# 3_1.net
KiCad netlist of a schematic drawn in Altium Designer
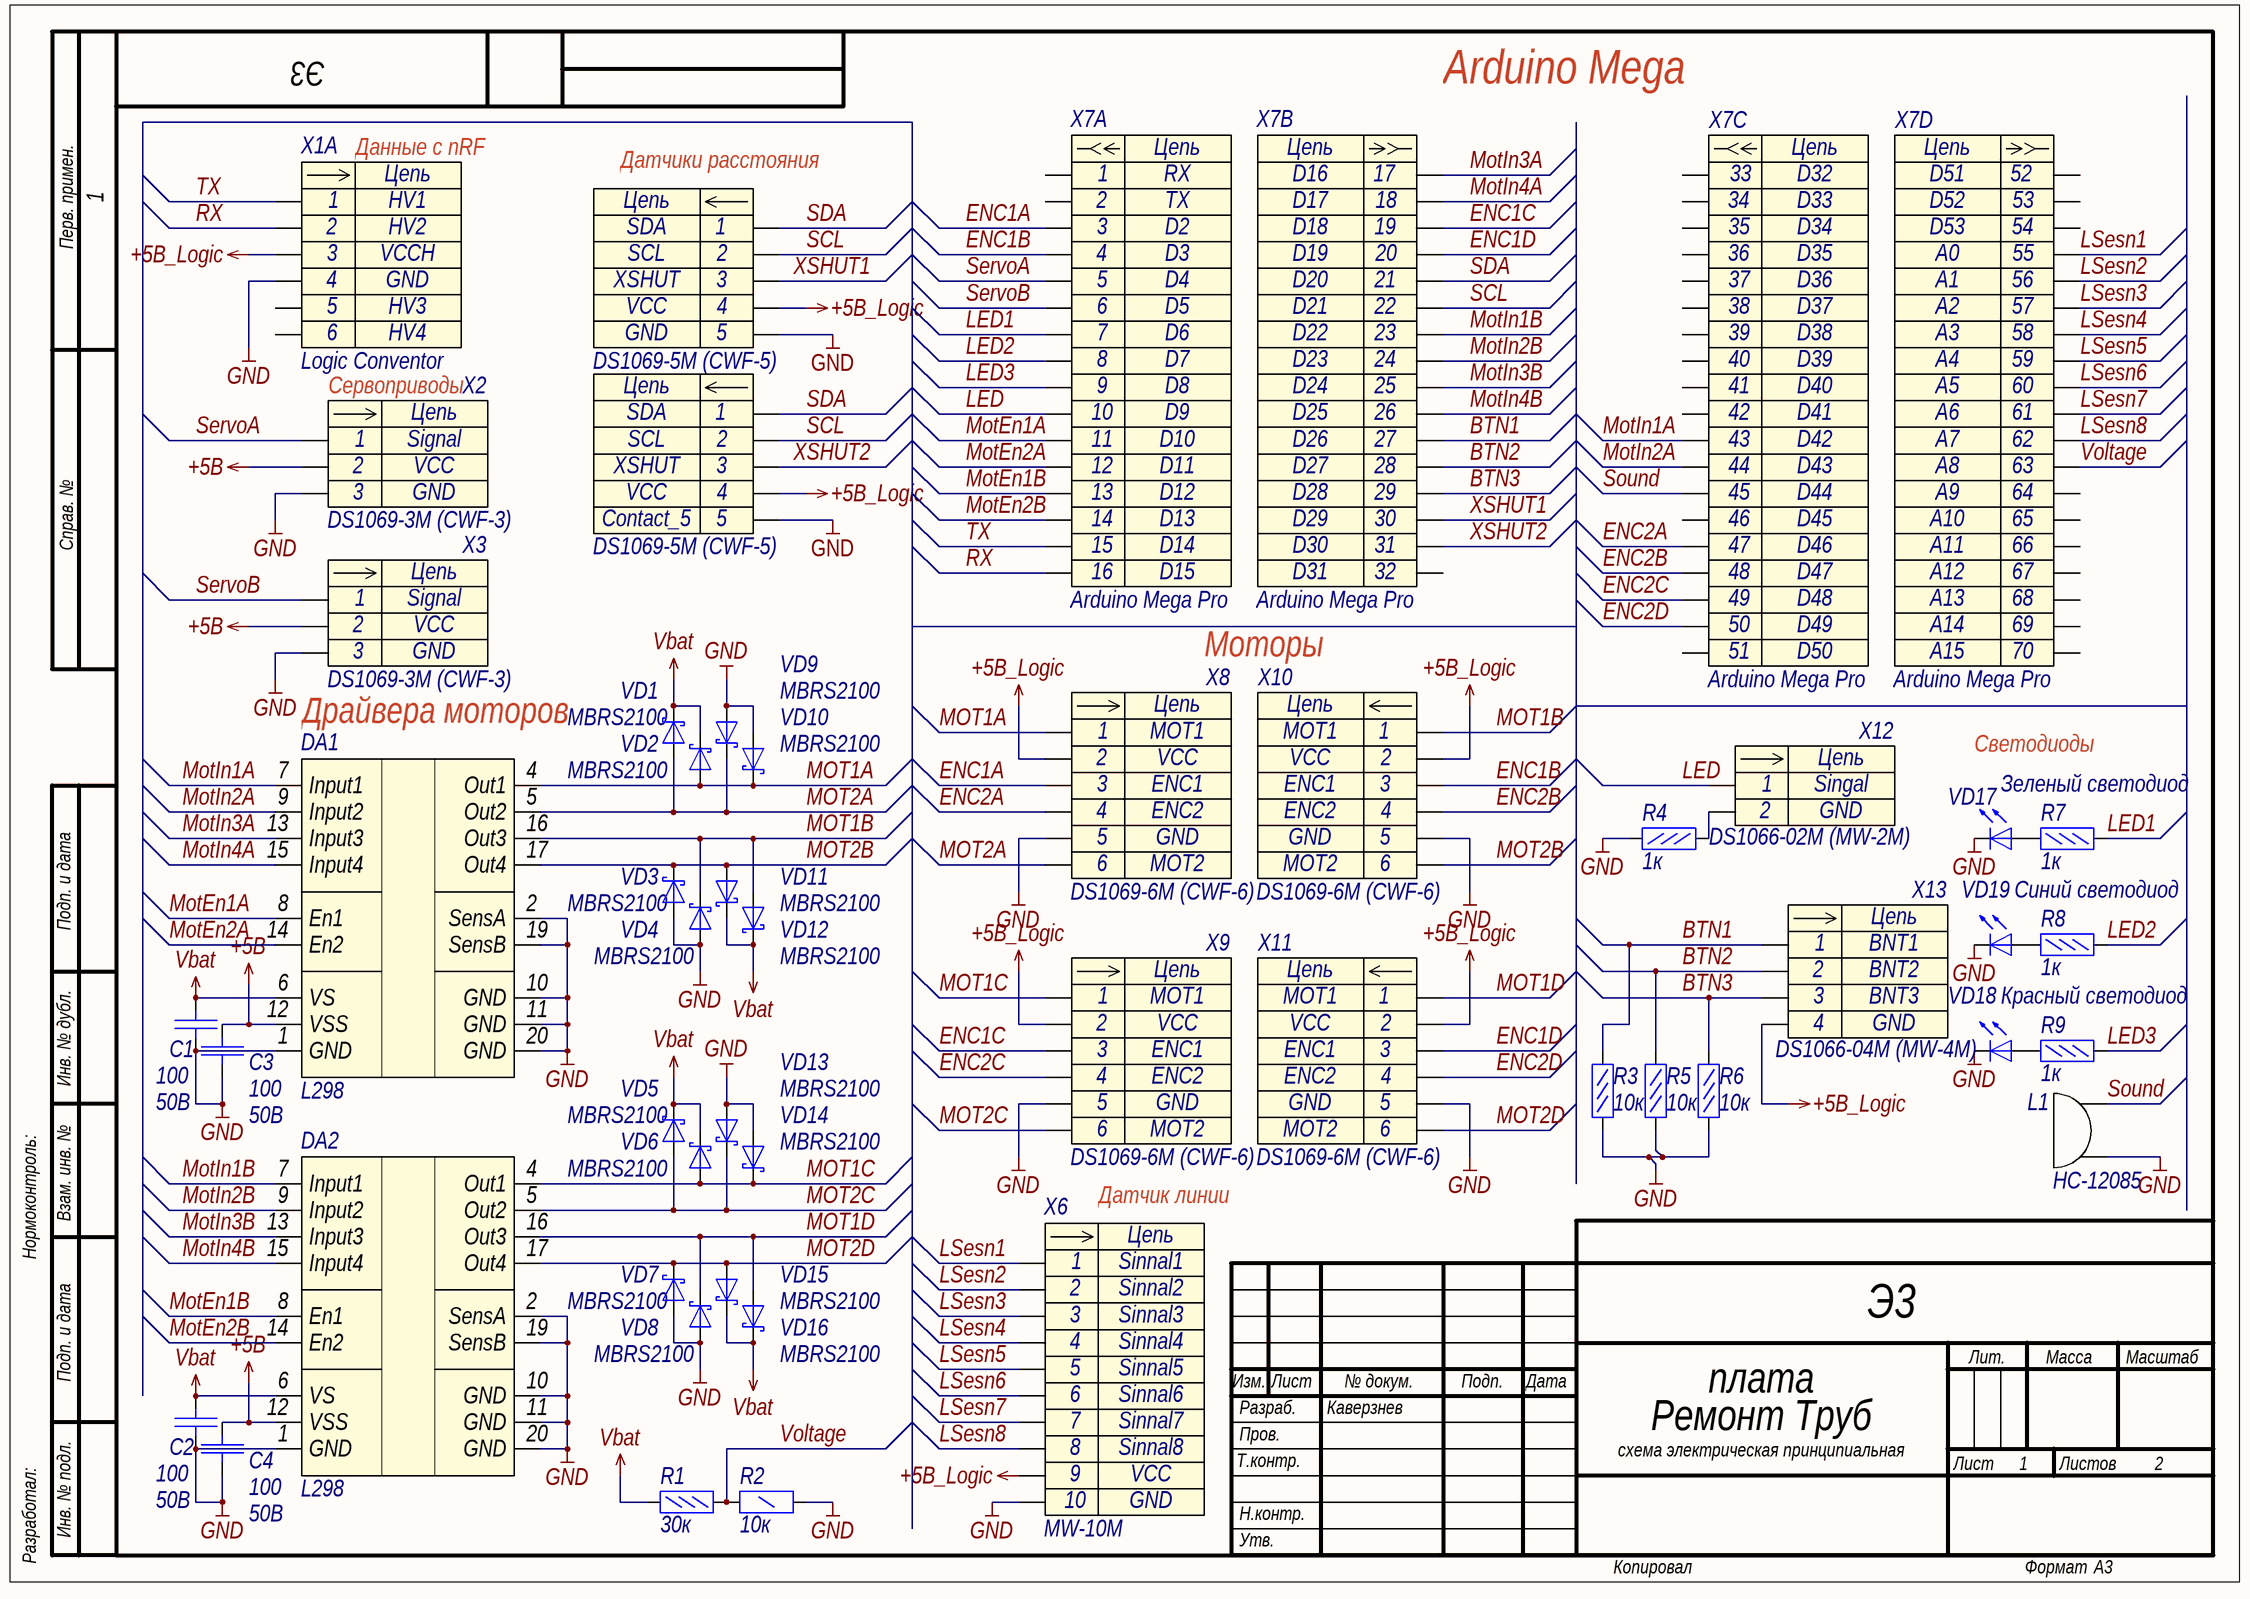
[diagram p0: Э3_1.SchDoc]

(export (version "E")
  (design (tool "Eeschema 10.0.6"))
  (components
    (comp (ref "C1")
      (value "100")
      (footprint "C0603")
      (description "Конденсатор кер. 100пФ 50В")
      (fields (field (name "MANUFACTURER") "Yageo") (field (name "VOLTAGE") "50В"))
      (libsource (lib "capacitors") (part "CC0603JRNPO9BN101"))
    )
    (comp (ref "C2")
      (value "100")
      (footprint "C0603")
      (description "Конденсатор кер. 100пФ 50В")
      (fields (field (name "MANUFACTURER") "Yageo") (field (name "VOLTAGE") "50В"))
      (libsource (lib "capacitors") (part "CC0603JRNPO9BN101"))
    )
    (comp (ref "C3")
      (value "100")
      (footprint "C0603")
      (description "Конденсатор кер. 100пФ 50В")
      (fields (field (name "MANUFACTURER") "Yageo") (field (name "VOLTAGE") "50В"))
      (libsource (lib "capacitors") (part "CC0603JRNPO9BN101"))
    )
    (comp (ref "C4")
      (value "100")
      (footprint "C0603")
      (description "Конденсатор кер. 100пФ 50В")
      (fields (field (name "MANUFACTURER") "Yageo") (field (name "VOLTAGE") "50В"))
      (libsource (lib "capacitors") (part "CC0603JRNPO9BN101"))
    )
    (comp (ref "DA1")
      (value "L298")
      (footprint "L298P")
      (description "Драйвер двигателя")
      (fields (field (name "MANUFACTURER") "China") (field (name "NAME") "L298"))
      (libsource (lib "ics") (part "L298"))
    )
    (comp (ref "DA2")
      (value "L298")
      (footprint "L298P")
      (description "Драйвер двигателя")
      (fields (field (name "MANUFACTURER") "China") (field (name "NAME") "L298"))
      (libsource (lib "ics") (part "L298"))
    )
    (comp (ref "L1")
      (value "HC-12085")
      (footprint "Buzzer")
      (fields (field (name "MANUFACTURER") "Epcos TDK") (field (name "NAME") "HC-12085"))
      (libsource (lib "ics") (part "HC-12085"))
    )
    (comp (ref "R1")
      (value "30к")
      (footprint "R0603")
      (description "Резистор 30кОм 0,063Вт 1%")
      (fields (field (name "MANUFACTURER") "YAGEO") (field (name "TOLERANCE") "1%"))
      (libsource (lib "resistors") (part "RC0603FR-0730KL"))
    )
    (comp (ref "R2")
      (value "10к")
      (footprint "R1206")
      (description "Резистор 10к 0,25Вт 1%")
      (fields (field (name "MANUFACTURER") "YAGEO"))
      (libsource (lib "resistors") (part "RC1206FR-0710KL"))
    )
    (comp (ref "R3")
      (value "10к")
      (footprint "R0603")
      (description "Резистор 10кОм 0,063Вт 1%")
      (fields (field (name "MANUFACTURER") "YAGEO") (field (name "TOLERANCE") "1%"))
      (libsource (lib "resistors") (part "RC0603FR-0710KL"))
    )
    (comp (ref "R4")
      (value "1к")
      (footprint "R0603")
      (description "Резистор 1кОм 0,063Вт 1%")
      (fields (field (name "MANUFACTURER") "YAGEO") (field (name "TOLERANCE") "1%"))
      (libsource (lib "") (part "RC0603FR-071KL_1"))
    )
    (comp (ref "R5")
      (value "10к")
      (footprint "R0603")
      (description "Резистор 10кОм 0,063Вт 1%")
      (fields (field (name "MANUFACTURER") "YAGEO") (field (name "TOLERANCE") "1%"))
      (libsource (lib "resistors") (part "RC0603FR-0710KL"))
    )
    (comp (ref "R6")
      (value "10к")
      (footprint "R0603")
      (description "Резистор 10кОм 0,063Вт 1%")
      (fields (field (name "MANUFACTURER") "YAGEO") (field (name "TOLERANCE") "1%"))
      (libsource (lib "resistors") (part "RC0603FR-0710KL"))
    )
    (comp (ref "R7")
      (value "1к")
      (footprint "R0603")
      (description "Резистор 1кОм 0,063Вт 1%")
      (fields (field (name "MANUFACTURER") "YAGEO") (field (name "TOLERANCE") "1%"))
      (libsource (lib "resistors") (part "RC0603FR-071KL"))
    )
    (comp (ref "R8")
      (value "1к")
      (footprint "R0603")
      (description "Резистор 1кОм 0,063Вт 1%")
      (fields (field (name "MANUFACTURER") "YAGEO") (field (name "TOLERANCE") "1%"))
      (libsource (lib "resistors") (part "RC0603FR-071KL"))
    )
    (comp (ref "R9")
      (value "1к")
      (footprint "R0603")
      (description "Резистор 1кОм 0,063Вт 1%")
      (fields (field (name "MANUFACTURER") "YAGEO") (field (name "TOLERANCE") "1%"))
      (libsource (lib "resistors") (part "RC0603FR-071KL"))
    )
    (comp (ref "VD1")
      (value "MBRS2100")
      (footprint "DO-214AA")
      (description "Диод Шоттки 100В 2А")
      (fields (field (name "NAME") "MBRS2100"))
      (libsource (lib "diodes") (part "MBRS2100"))
    )
    (comp (ref "VD2")
      (value "MBRS2100")
      (footprint "DO-214AA")
      (description "Диод Шоттки 100В 2А")
      (fields (field (name "NAME") "MBRS2100"))
      (libsource (lib "diodes") (part "MBRS2100"))
    )
    (comp (ref "VD3")
      (value "MBRS2100")
      (footprint "DO-214AA")
      (description "Диод Шоттки 100В 2А")
      (fields (field (name "NAME") "MBRS2100"))
      (libsource (lib "diodes") (part "MBRS2100"))
    )
    (comp (ref "VD4")
      (value "MBRS2100")
      (footprint "DO-214AA")
      (description "Диод Шоттки 100В 2А")
      (fields (field (name "NAME") "MBRS2100"))
      (libsource (lib "diodes") (part "MBRS2100"))
    )
    (comp (ref "VD5")
      (value "MBRS2100")
      (footprint "DO-214AA")
      (description "Диод Шоттки 100В 2А")
      (fields (field (name "NAME") "MBRS2100"))
      (libsource (lib "diodes") (part "MBRS2100"))
    )
    (comp (ref "VD6")
      (value "MBRS2100")
      (footprint "DO-214AA")
      (description "Диод Шоттки 100В 2А")
      (fields (field (name "NAME") "MBRS2100"))
      (libsource (lib "diodes") (part "MBRS2100"))
    )
    (comp (ref "VD7")
      (value "MBRS2100")
      (footprint "DO-214AA")
      (description "Диод Шоттки 100В 2А")
      (fields (field (name "NAME") "MBRS2100"))
      (libsource (lib "diodes") (part "MBRS2100"))
    )
    (comp (ref "VD8")
      (value "MBRS2100")
      (footprint "DO-214AA")
      (description "Диод Шоттки 100В 2А")
      (fields (field (name "NAME") "MBRS2100"))
      (libsource (lib "diodes") (part "MBRS2100"))
    )
    (comp (ref "VD9")
      (value "MBRS2100")
      (footprint "DO-214AA")
      (description "Диод Шоттки 100В 2А")
      (fields (field (name "NAME") "MBRS2100"))
      (libsource (lib "diodes") (part "MBRS2100"))
    )
    (comp (ref "VD10")
      (value "MBRS2100")
      (footprint "DO-214AA")
      (description "Диод Шоттки 100В 2А")
      (fields (field (name "NAME") "MBRS2100"))
      (libsource (lib "diodes") (part "MBRS2100"))
    )
    (comp (ref "VD11")
      (value "MBRS2100")
      (footprint "DO-214AA")
      (description "Диод Шоттки 100В 2А")
      (fields (field (name "NAME") "MBRS2100"))
      (libsource (lib "diodes") (part "MBRS2100"))
    )
    (comp (ref "VD12")
      (value "MBRS2100")
      (footprint "DO-214AA")
      (description "Диод Шоттки 100В 2А")
      (fields (field (name "NAME") "MBRS2100"))
      (libsource (lib "diodes") (part "MBRS2100"))
    )
    (comp (ref "VD13")
      (value "MBRS2100")
      (footprint "DO-214AA")
      (description "Диод Шоттки 100В 2А")
      (fields (field (name "NAME") "MBRS2100"))
      (libsource (lib "diodes") (part "MBRS2100"))
    )
    (comp (ref "VD14")
      (value "MBRS2100")
      (footprint "DO-214AA")
      (description "Диод Шоттки 100В 2А")
      (fields (field (name "NAME") "MBRS2100"))
      (libsource (lib "diodes") (part "MBRS2100"))
    )
    (comp (ref "VD15")
      (value "MBRS2100")
      (footprint "DO-214AA")
      (description "Диод Шоттки 100В 2А")
      (fields (field (name "NAME") "MBRS2100"))
      (libsource (lib "diodes") (part "MBRS2100"))
    )
    (comp (ref "VD16")
      (value "MBRS2100")
      (footprint "DO-214AA")
      (description "Диод Шоттки 100В 2А")
      (fields (field (name "NAME") "MBRS2100"))
      (libsource (lib "diodes") (part "MBRS2100"))
    )
    (comp (ref "VD17")
      (value "Зеленый светодиод")
      (footprint "VD0603")
      (description "Светодтод зеленый SMD Foryard Optoelectronics Co.")
      (libsource (lib "diodes") (part "FYLS-0603BUGC"))
    )
    (comp (ref "VD18")
      (value "Красный светодиод")
      (footprint "VD0603")
      (description "Светодтод красный SMD Foryard Optoelectronics Co.")
      (libsource (lib "diodes") (part "FYLS-0603BURC"))
    )
    (comp (ref "VD19")
      (value "Синий светодиод")
      (footprint "VD0603")
      (description "Светодтод синий SMD Foryard Optoelectronics Co.")
      (libsource (lib "diodes") (part "FYLS-0603BUBC"))
    )
    (comp (ref "X1")
      (value "Logic Conventor")
      (footprint "LOGIC CONVENTOR")
      (description "Преобразователь уровней")
      (fields (field (name "NAME") "Logic Conventor"))
      (libsource (lib "headers") (part "Logic Conventor"))
    )
    (comp (ref "X2")
      (value "DS1069-3M (CWF-3)")
      (footprint "CWF-3")
      (description "Разъем - 3 конт. прямая вилка на плату")
      (fields (field (name "NAME") "DS1069-3M (CWF-3)"))
      (libsource (lib "headers") (part "CWF-3"))
    )
    (comp (ref "X3")
      (value "DS1069-3M (CWF-3)")
      (footprint "CWF-3")
      (description "Разъем - 3 конт. прямая вилка на плату")
      (fields (field (name "NAME") "DS1069-3M (CWF-3)"))
      (libsource (lib "headers") (part "CWF-3"))
    )
    (comp (ref "X4")
      (value "DS1069-5M (CWF-5)")
      (footprint "CWF-5")
      (description "Разъем - 5 конт. прямая вилка на плату")
      (fields (field (name "NAME") "DS1069-5M (CWF-5)"))
      (libsource (lib "headers") (part "CWF-5"))
    )
    (comp (ref "X5")
      (value "DS1069-5M (CWF-5)")
      (footprint "CWF-5")
      (description "Разъем - 5 конт. прямая вилка на плату")
      (fields (field (name "NAME") "DS1069-5M (CWF-5)"))
      (libsource (lib "headers") (part "CWF-5"))
    )
    (comp (ref "X6")
      (value "MW-10M")
      (footprint "MW-10M")
      (description "CWF-10")
      (fields (field (name "NAME") "MW-10M"))
      (libsource (lib "headers") (part "CWF-10"))
    )
    (comp (ref "X7")
      (value "Arduino Mega Pro")
      (footprint "Arduino Mega Pro Mini")
      (description "Arduino Mega Pro Mini")
      (fields (field (name "NAME") "Arduino Mega Pro"))
      (libsource (lib "headers") (part "Arduino Mega Pro Mini"))
    )
    (comp (ref "X8")
      (value "DS1069-6M (CWF-6)")
      (footprint "CWF-6")
      (description "Разъем - 6 конт. прямая вилка на плату")
      (fields (field (name "NAME") "DS1069-6M (CWF-6)"))
      (libsource (lib "headers") (part "CWF-6"))
    )
    (comp (ref "X9")
      (value "DS1069-6M (CWF-6)")
      (footprint "CWF-6")
      (description "Разъем - 6 конт. прямая вилка на плату")
      (fields (field (name "NAME") "DS1069-6M (CWF-6)"))
      (libsource (lib "headers") (part "CWF-6"))
    )
    (comp (ref "X10")
      (value "DS1069-6M (CWF-6)")
      (footprint "CWF-6")
      (description "Разъем - 6 конт. прямая вилка на плату")
      (fields (field (name "NAME") "DS1069-6M (CWF-6)"))
      (libsource (lib "") (part "CWF-6_1"))
    )
    (comp (ref "X11")
      (value "DS1069-6M (CWF-6)")
      (footprint "CWF-6")
      (description "Разъем - 6 конт. прямая вилка на плату")
      (fields (field (name "NAME") "DS1069-6M (CWF-6)"))
      (libsource (lib "") (part "CWF-6_1"))
    )
    (comp (ref "X12")
      (value "DS1066-02M (MW-2M)")
      (footprint "MW-2M")
      (description "Разъем - 2 конт. прямая вилка на плату")
      (fields (field (name "NAME") "DS1066-02M (MW-2M)"))
      (libsource (lib "headers") (part "MW-2M"))
    )
    (comp (ref "X13")
      (value "DS1066-04M (MW-4M)")
      (footprint "MW-4M")
      (description "Разъем - 4 конт. прямая вилка на плату")
      (fields (field (name "NAME") "DS1066-04M (MW-4M)"))
      (libsource (lib "headers") (part "MW-4M"))
    )
  )
  (nets
    (net (code "1") (name "+5B") (class "Default")
      (node (ref "C3") (pin "2") (pinfunction "2_2") (pintype "passive"))
      (node (ref "C4") (pin "2") (pinfunction "2_2") (pintype "passive"))
      (node (ref "DA1") (pin "12") (pinfunction "VSS_12") (pintype "passive"))
      (node (ref "DA2") (pin "12") (pinfunction "VSS_12") (pintype "passive"))
      (node (ref "X2") (pin "2") (pinfunction "2_2") (pintype "passive"))
      (node (ref "X3") (pin "2") (pinfunction "2_2") (pintype "passive"))
    )
    (net (code "2") (name "+5B_Logic") (class "Default")
      (node (ref "X1") (pin "3") (pinfunction "3_3") (pintype "passive"))
      (node (ref "X10") (pin "2") (pinfunction "2_2") (pintype "passive"))
      (node (ref "X11") (pin "2") (pinfunction "2_2") (pintype "passive"))
      (node (ref "X13") (pin "4") (pinfunction "4_4") (pintype "passive"))
      (node (ref "X4") (pin "4") (pinfunction "4_4") (pintype "passive"))
      (node (ref "X5") (pin "4") (pinfunction "4_4") (pintype "passive"))
      (node (ref "X6") (pin "9") (pinfunction "9_9") (pintype "passive"))
      (node (ref "X8") (pin "2") (pinfunction "2_2") (pintype "passive"))
      (node (ref "X9") (pin "2") (pinfunction "2_2") (pintype "passive"))
    )
    (net (code "3") (name "/BTN1") (class "Default")
      (node (ref "R3") (pin "2") (pinfunction "2_2") (pintype "passive"))
      (node (ref "X13") (pin "1") (pinfunction "1_1") (pintype "passive"))
      (node (ref "X7") (pin "27") (pinfunction "27_27") (pintype "passive"))
    )
    (net (code "4") (name "/BTN2") (class "Default")
      (node (ref "R5") (pin "2") (pinfunction "2_2") (pintype "passive"))
      (node (ref "X13") (pin "2") (pinfunction "2_2") (pintype "passive"))
      (node (ref "X7") (pin "28") (pinfunction "28_28") (pintype "passive"))
    )
    (net (code "5") (name "/BTN3") (class "Default")
      (node (ref "R6") (pin "2") (pinfunction "2_2") (pintype "passive"))
      (node (ref "X13") (pin "3") (pinfunction "3_3") (pintype "passive"))
      (node (ref "X7") (pin "29") (pinfunction "29_29") (pintype "passive"))
    )
    (net (code "6") (name "/ENC1A") (class "Default")
      (node (ref "X7") (pin "3") (pinfunction "3_3") (pintype "passive"))
      (node (ref "X8") (pin "3") (pinfunction "3_3") (pintype "passive"))
    )
    (net (code "7") (name "/ENC1B") (class "Default")
      (node (ref "X10") (pin "3") (pinfunction "3_3") (pintype "passive"))
      (node (ref "X7") (pin "4") (pinfunction "4_4") (pintype "passive"))
    )
    (net (code "8") (name "/ENC1C") (class "Default")
      (node (ref "X7") (pin "19") (pinfunction "19_19") (pintype "passive"))
      (node (ref "X9") (pin "3") (pinfunction "3_3") (pintype "passive"))
    )
    (net (code "9") (name "/ENC1D") (class "Default")
      (node (ref "X11") (pin "3") (pinfunction "3_3") (pintype "passive"))
      (node (ref "X7") (pin "20") (pinfunction "20_20") (pintype "passive"))
    )
    (net (code "10") (name "/ENC2A") (class "Default")
      (node (ref "X7") (pin "47") (pinfunction "47_47") (pintype "passive"))
      (node (ref "X8") (pin "4") (pinfunction "4_4") (pintype "passive"))
    )
    (net (code "11") (name "/ENC2B") (class "Default")
      (node (ref "X10") (pin "4") (pinfunction "4_4") (pintype "passive"))
      (node (ref "X7") (pin "48") (pinfunction "48_48") (pintype "passive"))
    )
    (net (code "12") (name "/ENC2C") (class "Default")
      (node (ref "X7") (pin "49") (pinfunction "49_49") (pintype "passive"))
      (node (ref "X9") (pin "4") (pinfunction "4_4") (pintype "passive"))
    )
    (net (code "13") (name "/ENC2D") (class "Default")
      (node (ref "X11") (pin "4") (pinfunction "4_4") (pintype "passive"))
      (node (ref "X7") (pin "50") (pinfunction "50_50") (pintype "passive"))
    )
    (net (code "14") (name "/LED") (class "Default")
      (node (ref "X12") (pin "1") (pinfunction "1_1") (pintype "passive"))
      (node (ref "X7") (pin "10") (pinfunction "10_10") (pintype "passive"))
    )
    (net (code "15") (name "/LED1") (class "Default")
      (node (ref "R7") (pin "2") (pinfunction "2_2") (pintype "passive"))
      (node (ref "X7") (pin "7") (pinfunction "7_7") (pintype "passive"))
    )
    (net (code "16") (name "/LED2") (class "Default")
      (node (ref "R8") (pin "2") (pinfunction "2_2") (pintype "passive"))
      (node (ref "X7") (pin "8") (pinfunction "8_8") (pintype "passive"))
    )
    (net (code "17") (name "/LED3") (class "Default")
      (node (ref "R9") (pin "2") (pinfunction "2_2") (pintype "passive"))
      (node (ref "X7") (pin "9") (pinfunction "9_9") (pintype "passive"))
    )
    (net (code "18") (name "/LSesn1") (class "Default")
      (node (ref "X6") (pin "1") (pinfunction "1_1") (pintype "passive"))
      (node (ref "X7") (pin "55") (pinfunction "55_55") (pintype "passive"))
    )
    (net (code "19") (name "/LSesn2") (class "Default")
      (node (ref "X6") (pin "2") (pinfunction "2_2") (pintype "passive"))
      (node (ref "X7") (pin "56") (pinfunction "56_56") (pintype "passive"))
    )
    (net (code "20") (name "/LSesn3") (class "Default")
      (node (ref "X6") (pin "3") (pinfunction "3_3") (pintype "passive"))
      (node (ref "X7") (pin "57") (pinfunction "57_57") (pintype "passive"))
    )
    (net (code "21") (name "/LSesn4") (class "Default")
      (node (ref "X6") (pin "4") (pinfunction "4_4") (pintype "passive"))
      (node (ref "X7") (pin "58") (pinfunction "58_58") (pintype "passive"))
    )
    (net (code "22") (name "/LSesn5") (class "Default")
      (node (ref "X6") (pin "5") (pinfunction "5_5") (pintype "passive"))
      (node (ref "X7") (pin "59") (pinfunction "59_59") (pintype "passive"))
    )
    (net (code "23") (name "/LSesn6") (class "Default")
      (node (ref "X6") (pin "6") (pinfunction "6_6") (pintype "passive"))
      (node (ref "X7") (pin "60") (pinfunction "60_60") (pintype "passive"))
    )
    (net (code "24") (name "/LSesn7") (class "Default")
      (node (ref "X6") (pin "7") (pinfunction "7_7") (pintype "passive"))
      (node (ref "X7") (pin "61") (pinfunction "61_61") (pintype "passive"))
    )
    (net (code "25") (name "/LSesn8") (class "Default")
      (node (ref "X6") (pin "8") (pinfunction "8_8") (pintype "passive"))
      (node (ref "X7") (pin "62") (pinfunction "62_62") (pintype "passive"))
    )
    (net (code "26") (name "/MOT1A") (class "Default")
      (node (ref "DA1") (pin "4") (pinfunction "Out1_4") (pintype "passive"))
      (node (ref "VD10") (pin "1") (pinfunction "K_1") (pintype "passive"))
      (node (ref "VD2") (pin "2") (pinfunction "A_2") (pintype "passive"))
      (node (ref "X8") (pin "1") (pinfunction "1_1") (pintype "passive"))
    )
    (net (code "27") (name "/MOT1B") (class "Default")
      (node (ref "DA1") (pin "16") (pinfunction "Out3_16") (pintype "passive"))
      (node (ref "VD12") (pin "2") (pinfunction "A_2") (pintype "passive"))
      (node (ref "VD4") (pin "1") (pinfunction "K_1") (pintype "passive"))
      (node (ref "X10") (pin "1") (pinfunction "1_1") (pintype "passive"))
    )
    (net (code "28") (name "/MOT1C") (class "Default")
      (node (ref "DA2") (pin "4") (pinfunction "Out1_4") (pintype "passive"))
      (node (ref "VD14") (pin "1") (pinfunction "K_1") (pintype "passive"))
      (node (ref "VD6") (pin "2") (pinfunction "A_2") (pintype "passive"))
      (node (ref "X9") (pin "1") (pinfunction "1_1") (pintype "passive"))
    )
    (net (code "29") (name "/MOT1D") (class "Default")
      (node (ref "DA2") (pin "16") (pinfunction "Out3_16") (pintype "passive"))
      (node (ref "VD16") (pin "2") (pinfunction "A_2") (pintype "passive"))
      (node (ref "VD8") (pin "1") (pinfunction "K_1") (pintype "passive"))
      (node (ref "X11") (pin "1") (pinfunction "1_1") (pintype "passive"))
    )
    (net (code "30") (name "/MOT2A") (class "Default")
      (node (ref "DA1") (pin "5") (pinfunction "Out2_5") (pintype "passive"))
      (node (ref "VD1") (pin "2") (pinfunction "A_2") (pintype "passive"))
      (node (ref "VD9") (pin "1") (pinfunction "K_1") (pintype "passive"))
      (node (ref "X8") (pin "6") (pinfunction "6_6") (pintype "passive"))
    )
    (net (code "31") (name "/MOT2B") (class "Default")
      (node (ref "DA1") (pin "17") (pinfunction "Out4_17") (pintype "passive"))
      (node (ref "VD11") (pin "2") (pinfunction "A_2") (pintype "passive"))
      (node (ref "VD3") (pin "1") (pinfunction "K_1") (pintype "passive"))
      (node (ref "X10") (pin "6") (pinfunction "6_6") (pintype "passive"))
    )
    (net (code "32") (name "/MOT2C") (class "Default")
      (node (ref "DA2") (pin "5") (pinfunction "Out2_5") (pintype "passive"))
      (node (ref "VD13") (pin "1") (pinfunction "K_1") (pintype "passive"))
      (node (ref "VD5") (pin "2") (pinfunction "A_2") (pintype "passive"))
      (node (ref "X9") (pin "6") (pinfunction "6_6") (pintype "passive"))
    )
    (net (code "33") (name "/MOT2D") (class "Default")
      (node (ref "DA2") (pin "17") (pinfunction "Out4_17") (pintype "passive"))
      (node (ref "VD15") (pin "2") (pinfunction "A_2") (pintype "passive"))
      (node (ref "VD7") (pin "1") (pinfunction "K_1") (pintype "passive"))
      (node (ref "X11") (pin "6") (pinfunction "6_6") (pintype "passive"))
    )
    (net (code "34") (name "/MotEn1A") (class "Default")
      (node (ref "DA1") (pin "8") (pinfunction "En1_8") (pintype "passive"))
      (node (ref "X7") (pin "11") (pinfunction "11_11") (pintype "passive"))
    )
    (net (code "35") (name "/MotEn1B") (class "Default")
      (node (ref "DA2") (pin "8") (pinfunction "En1_8") (pintype "passive"))
      (node (ref "X7") (pin "13") (pinfunction "13_13") (pintype "passive"))
    )
    (net (code "36") (name "/MotEn2A") (class "Default")
      (node (ref "DA1") (pin "14") (pinfunction "En2_14") (pintype "passive"))
      (node (ref "X7") (pin "12") (pinfunction "12_12") (pintype "passive"))
    )
    (net (code "37") (name "/MotEn2B") (class "Default")
      (node (ref "DA2") (pin "14") (pinfunction "En2_14") (pintype "passive"))
      (node (ref "X7") (pin "14") (pinfunction "14_14") (pintype "passive"))
    )
    (net (code "38") (name "/MotIn1A") (class "Default")
      (node (ref "DA1") (pin "7") (pinfunction "Input1_7") (pintype "passive"))
      (node (ref "X7") (pin "15") (pinfunction "15_15") (pintype "passive"))
    )
    (net (code "39") (name "/MotIn1B") (class "Default")
      (node (ref "DA2") (pin "7") (pinfunction "Input1_7") (pintype "passive"))
      (node (ref "X7") (pin "23") (pinfunction "23_23") (pintype "passive"))
    )
    (net (code "40") (name "/MotIn2A") (class "Default")
      (node (ref "DA1") (pin "9") (pinfunction "Input2_9") (pintype "passive"))
      (node (ref "X7") (pin "16") (pinfunction "16_16") (pintype "passive"))
    )
    (net (code "41") (name "/MotIn2B") (class "Default")
      (node (ref "DA2") (pin "9") (pinfunction "Input2_9") (pintype "passive"))
      (node (ref "X7") (pin "24") (pinfunction "24_24") (pintype "passive"))
    )
    (net (code "42") (name "/MotIn3A") (class "Default")
      (node (ref "DA1") (pin "13") (pinfunction "Input3_13") (pintype "passive"))
      (node (ref "X7") (pin "17") (pinfunction "17_17") (pintype "passive"))
    )
    (net (code "43") (name "/MotIn3B") (class "Default")
      (node (ref "DA2") (pin "13") (pinfunction "Input3_13") (pintype "passive"))
      (node (ref "X7") (pin "25") (pinfunction "25_25") (pintype "passive"))
    )
    (net (code "44") (name "/MotIn4A") (class "Default")
      (node (ref "DA1") (pin "15") (pinfunction "Input4_15") (pintype "passive"))
      (node (ref "X7") (pin "18") (pinfunction "18_18") (pintype "passive"))
    )
    (net (code "45") (name "/MotIn4B") (class "Default")
      (node (ref "DA2") (pin "15") (pinfunction "Input4_15") (pintype "passive"))
      (node (ref "X7") (pin "26") (pinfunction "26_26") (pintype "passive"))
    )
    (net (code "46") (name "/RX") (class "Default")
      (node (ref "X1") (pin "2") (pinfunction "2_2") (pintype "passive"))
      (node (ref "X7") (pin "31") (pinfunction "31_31") (pintype "passive"))
    )
    (net (code "47") (name "/SCL") (class "Default")
      (node (ref "X4") (pin "2") (pinfunction "2_2") (pintype "passive"))
      (node (ref "X5") (pin "2") (pinfunction "2_2") (pintype "passive"))
      (node (ref "X7") (pin "22") (pinfunction "22_22") (pintype "passive"))
    )
    (net (code "48") (name "/SDA") (class "Default")
      (node (ref "X4") (pin "1") (pinfunction "1_1") (pintype "passive"))
      (node (ref "X5") (pin "1") (pinfunction "1_1") (pintype "passive"))
      (node (ref "X7") (pin "21") (pinfunction "21_21") (pintype "passive"))
    )
    (net (code "49") (name "/ServoA") (class "Default")
      (node (ref "X2") (pin "1") (pinfunction "1_1") (pintype "passive"))
      (node (ref "X7") (pin "5") (pinfunction "5_5") (pintype "passive"))
    )
    (net (code "50") (name "/ServoB") (class "Default")
      (node (ref "X3") (pin "1") (pinfunction "1_1") (pintype "passive"))
      (node (ref "X7") (pin "6") (pinfunction "6_6") (pintype "passive"))
    )
    (net (code "51") (name "/Sound") (class "Default")
      (node (ref "L1") (pin "1") (pinfunction "1_1") (pintype "passive"))
      (node (ref "X7") (pin "45") (pinfunction "45_45") (pintype "passive"))
    )
    (net (code "52") (name "/TX") (class "Default")
      (node (ref "X1") (pin "1") (pinfunction "1_1") (pintype "passive"))
      (node (ref "X7") (pin "30") (pinfunction "30_30") (pintype "passive"))
    )
    (net (code "53") (name "/Voltage") (class "Default")
      (node (ref "R1") (pin "2") (pinfunction "2_2") (pintype "passive"))
      (node (ref "R2") (pin "1") (pinfunction "1_1") (pintype "passive"))
      (node (ref "X7") (pin "43") (pinfunction "43_43") (pintype "passive"))
    )
    (net (code "54") (name "/XSHUT1") (class "Default")
      (node (ref "X4") (pin "3") (pinfunction "3_3") (pintype "passive"))
      (node (ref "X7") (pin "64") (pinfunction "64_64") (pintype "passive"))
    )
    (net (code "55") (name "/XSHUT2") (class "Default")
      (node (ref "X5") (pin "3") (pinfunction "3_3") (pintype "passive"))
      (node (ref "X7") (pin "65") (pinfunction "65_65") (pintype "passive"))
    )
    (net (code "56") (name "GND") (class "Default")
      (node (ref "C1") (pin "1") (pinfunction "1_1") (pintype "passive"))
      (node (ref "C2") (pin "1") (pinfunction "1_1") (pintype "passive"))
      (node (ref "C3") (pin "1") (pinfunction "1_1") (pintype "passive"))
      (node (ref "C4") (pin "1") (pinfunction "1_1") (pintype "passive"))
      (node (ref "DA1") (pin "1") (pinfunction "GND_1") (pintype "passive"))
      (node (ref "DA1") (pin "10") (pinfunction "GND_10") (pintype "passive"))
      (node (ref "DA1") (pin "11") (pinfunction "GND_11") (pintype "passive"))
      (node (ref "DA1") (pin "19") (pinfunction "SensB_19") (pintype "passive"))
      (node (ref "DA1") (pin "2") (pinfunction "SensA_2") (pintype "passive"))
      (node (ref "DA1") (pin "20") (pinfunction "GND_20") (pintype "passive"))
      (node (ref "DA2") (pin "1") (pinfunction "GND_1") (pintype "passive"))
      (node (ref "DA2") (pin "10") (pinfunction "GND_10") (pintype "passive"))
      (node (ref "DA2") (pin "11") (pinfunction "GND_11") (pintype "passive"))
      (node (ref "DA2") (pin "19") (pinfunction "SensB_19") (pintype "passive"))
      (node (ref "DA2") (pin "2") (pinfunction "SensA_2") (pintype "passive"))
      (node (ref "DA2") (pin "20") (pinfunction "GND_20") (pintype "passive"))
      (node (ref "L1") (pin "2") (pinfunction "2_2") (pintype "passive"))
      (node (ref "R2") (pin "2") (pinfunction "2_2") (pintype "passive"))
      (node (ref "R3") (pin "1") (pinfunction "1_1") (pintype "passive"))
      (node (ref "R4") (pin "2") (pinfunction "2_2") (pintype "passive"))
      (node (ref "R5") (pin "1") (pinfunction "1_1") (pintype "passive"))
      (node (ref "R6") (pin "1") (pinfunction "1_1") (pintype "passive"))
      (node (ref "VD10") (pin "2") (pinfunction "A_2") (pintype "passive"))
      (node (ref "VD13") (pin "2") (pinfunction "A_2") (pintype "passive"))
      (node (ref "VD14") (pin "2") (pinfunction "A_2") (pintype "passive"))
      (node (ref "VD17") (pin "2") (pinfunction "K_2") (pintype "passive"))
      (node (ref "VD18") (pin "2") (pinfunction "K_2") (pintype "passive"))
      (node (ref "VD19") (pin "2") (pinfunction "K_2") (pintype "passive"))
      (node (ref "VD3") (pin "2") (pinfunction "A_2") (pintype "passive"))
      (node (ref "VD4") (pin "2") (pinfunction "A_2") (pintype "passive"))
      (node (ref "VD7") (pin "2") (pinfunction "A_2") (pintype "passive"))
      (node (ref "VD8") (pin "2") (pinfunction "A_2") (pintype "passive"))
      (node (ref "VD9") (pin "2") (pinfunction "A_2") (pintype "passive"))
      (node (ref "X1") (pin "4") (pinfunction "4_4") (pintype "passive"))
      (node (ref "X10") (pin "5") (pinfunction "5_5") (pintype "passive"))
      (node (ref "X11") (pin "5") (pinfunction "5_5") (pintype "passive"))
      (node (ref "X2") (pin "3") (pinfunction "3_3") (pintype "passive"))
      (node (ref "X3") (pin "3") (pinfunction "3_3") (pintype "passive"))
      (node (ref "X4") (pin "5") (pinfunction "5_5") (pintype "passive"))
      (node (ref "X5") (pin "5") (pinfunction "5_5") (pintype "passive"))
      (node (ref "X6") (pin "10") (pinfunction "10_10") (pintype "passive"))
      (node (ref "X8") (pin "5") (pinfunction "5_5") (pintype "passive"))
      (node (ref "X9") (pin "5") (pinfunction "5_5") (pintype "passive"))
    )
    (net (code "57") (name "Net-(R4-Pad1)") (class "Default")
      (node (ref "R4") (pin "1") (pinfunction "1_1") (pintype "passive"))
      (node (ref "X12") (pin "2") (pinfunction "2_2") (pintype "passive"))
    )
    (net (code "58") (name "Net-(VD17-A)") (class "Default")
      (node (ref "R7") (pin "1") (pinfunction "1_1") (pintype "passive"))
      (node (ref "VD17") (pin "1") (pinfunction "A_1") (pintype "passive"))
    )
    (net (code "59") (name "Net-(VD18-A)") (class "Default")
      (node (ref "R9") (pin "1") (pinfunction "1_1") (pintype "passive"))
      (node (ref "VD18") (pin "1") (pinfunction "A_1") (pintype "passive"))
    )
    (net (code "60") (name "Net-(VD19-A)") (class "Default")
      (node (ref "R8") (pin "1") (pinfunction "1_1") (pintype "passive"))
      (node (ref "VD19") (pin "1") (pinfunction "A_1") (pintype "passive"))
    )
    (net (code "61") (name "Vbat") (class "Default")
      (node (ref "C1") (pin "2") (pinfunction "2_2") (pintype "passive"))
      (node (ref "C2") (pin "2") (pinfunction "2_2") (pintype "passive"))
      (node (ref "DA1") (pin "6") (pinfunction "VS_6") (pintype "passive"))
      (node (ref "DA2") (pin "6") (pinfunction "VS_6") (pintype "passive"))
      (node (ref "R1") (pin "1") (pinfunction "1_1") (pintype "passive"))
      (node (ref "VD1") (pin "1") (pinfunction "K_1") (pintype "passive"))
      (node (ref "VD11") (pin "1") (pinfunction "K_1") (pintype "passive"))
      (node (ref "VD12") (pin "1") (pinfunction "K_1") (pintype "passive"))
      (node (ref "VD15") (pin "1") (pinfunction "K_1") (pintype "passive"))
      (node (ref "VD16") (pin "1") (pinfunction "K_1") (pintype "passive"))
      (node (ref "VD2") (pin "1") (pinfunction "K_1") (pintype "passive"))
      (node (ref "VD5") (pin "1") (pinfunction "K_1") (pintype "passive"))
      (node (ref "VD6") (pin "1") (pinfunction "K_1") (pintype "passive"))
    )
    (net (code "62") (name "unconnected-(X1-Pad5)") (class "Default")
      (node (ref "X1") (pin "5") (pinfunction "5_5") (pintype "passive"))
    )
    (net (code "63") (name "unconnected-(X1-Pad6)") (class "Default")
      (node (ref "X1") (pin "6") (pinfunction "6_6") (pintype "passive"))
    )
    (net (code "64") (name "unconnected-(X7-Pad1)") (class "Default")
      (node (ref "X7") (pin "1") (pinfunction "1_1") (pintype "passive"))
    )
    (net (code "65") (name "unconnected-(X7-Pad2)") (class "Default")
      (node (ref "X7") (pin "2") (pinfunction "2_2") (pintype "passive"))
    )
    (net (code "66") (name "unconnected-(X7-Pad32)") (class "Default")
      (node (ref "X7") (pin "32") (pinfunction "32_32") (pintype "passive"))
    )
    (net (code "67") (name "unconnected-(X7-Pad33)") (class "Default")
      (node (ref "X7") (pin "33") (pinfunction "33_33") (pintype "passive"))
    )
    (net (code "68") (name "unconnected-(X7-Pad34)") (class "Default")
      (node (ref "X7") (pin "34") (pinfunction "34_34") (pintype "passive"))
    )
    (net (code "69") (name "unconnected-(X7-Pad35)") (class "Default")
      (node (ref "X7") (pin "35") (pinfunction "35_35") (pintype "passive"))
    )
    (net (code "70") (name "unconnected-(X7-Pad36)") (class "Default")
      (node (ref "X7") (pin "36") (pinfunction "36_36") (pintype "passive"))
    )
    (net (code "71") (name "unconnected-(X7-Pad37)") (class "Default")
      (node (ref "X7") (pin "37") (pinfunction "37_37") (pintype "passive"))
    )
    (net (code "72") (name "unconnected-(X7-Pad38)") (class "Default")
      (node (ref "X7") (pin "38") (pinfunction "38_38") (pintype "passive"))
    )
    (net (code "73") (name "unconnected-(X7-Pad39)") (class "Default")
      (node (ref "X7") (pin "39") (pinfunction "39_39") (pintype "passive"))
    )
    (net (code "74") (name "unconnected-(X7-Pad40)") (class "Default")
      (node (ref "X7") (pin "40") (pinfunction "40_40") (pintype "passive"))
    )
    (net (code "75") (name "unconnected-(X7-Pad41)") (class "Default")
      (node (ref "X7") (pin "41") (pinfunction "41_41") (pintype "passive"))
    )
    (net (code "76") (name "unconnected-(X7-Pad42)") (class "Default")
      (node (ref "X7") (pin "42") (pinfunction "42_42") (pintype "passive"))
    )
    (net (code "77") (name "unconnected-(X7-Pad44)") (class "Default")
      (node (ref "X7") (pin "44") (pinfunction "44_44") (pintype "passive"))
    )
    (net (code "78") (name "unconnected-(X7-Pad46)") (class "Default")
      (node (ref "X7") (pin "46") (pinfunction "46_46") (pintype "passive"))
    )
    (net (code "79") (name "unconnected-(X7-Pad51)") (class "Default")
      (node (ref "X7") (pin "51") (pinfunction "51_51") (pintype "passive"))
    )
    (net (code "80") (name "unconnected-(X7-Pad52)") (class "Default")
      (node (ref "X7") (pin "52") (pinfunction "52_52") (pintype "passive"))
    )
    (net (code "81") (name "unconnected-(X7-Pad53)") (class "Default")
      (node (ref "X7") (pin "53") (pinfunction "53_53") (pintype "passive"))
    )
    (net (code "82") (name "unconnected-(X7-Pad54)") (class "Default")
      (node (ref "X7") (pin "54") (pinfunction "54_54") (pintype "passive"))
    )
    (net (code "83") (name "unconnected-(X7-Pad65)") (class "Default")
      (node (ref "X7") (pin "65") (pinfunction "65_65") (pintype "passive"))
    )
    (net (code "84") (name "unconnected-(X7-Pad66)") (class "Default")
      (node (ref "X7") (pin "66") (pinfunction "66_66") (pintype "passive"))
    )
    (net (code "85") (name "unconnected-(X7-Pad67)") (class "Default")
      (node (ref "X7") (pin "67") (pinfunction "67_67") (pintype "passive"))
    )
    (net (code "86") (name "unconnected-(X7-Pad68)") (class "Default")
      (node (ref "X7") (pin "68") (pinfunction "68_68") (pintype "passive"))
    )
    (net (code "87") (name "unconnected-(X7-Pad69)") (class "Default")
      (node (ref "X7") (pin "69") (pinfunction "69_69") (pintype "passive"))
    )
    (net (code "88") (name "unconnected-(X7-Pad70)") (class "Default")
      (node (ref "X7") (pin "70") (pinfunction "70_70") (pintype "passive"))
    )
  )
)
